# Multiplier_AD835.net
KiCad netlist of a schematic drawn in Altium Designer
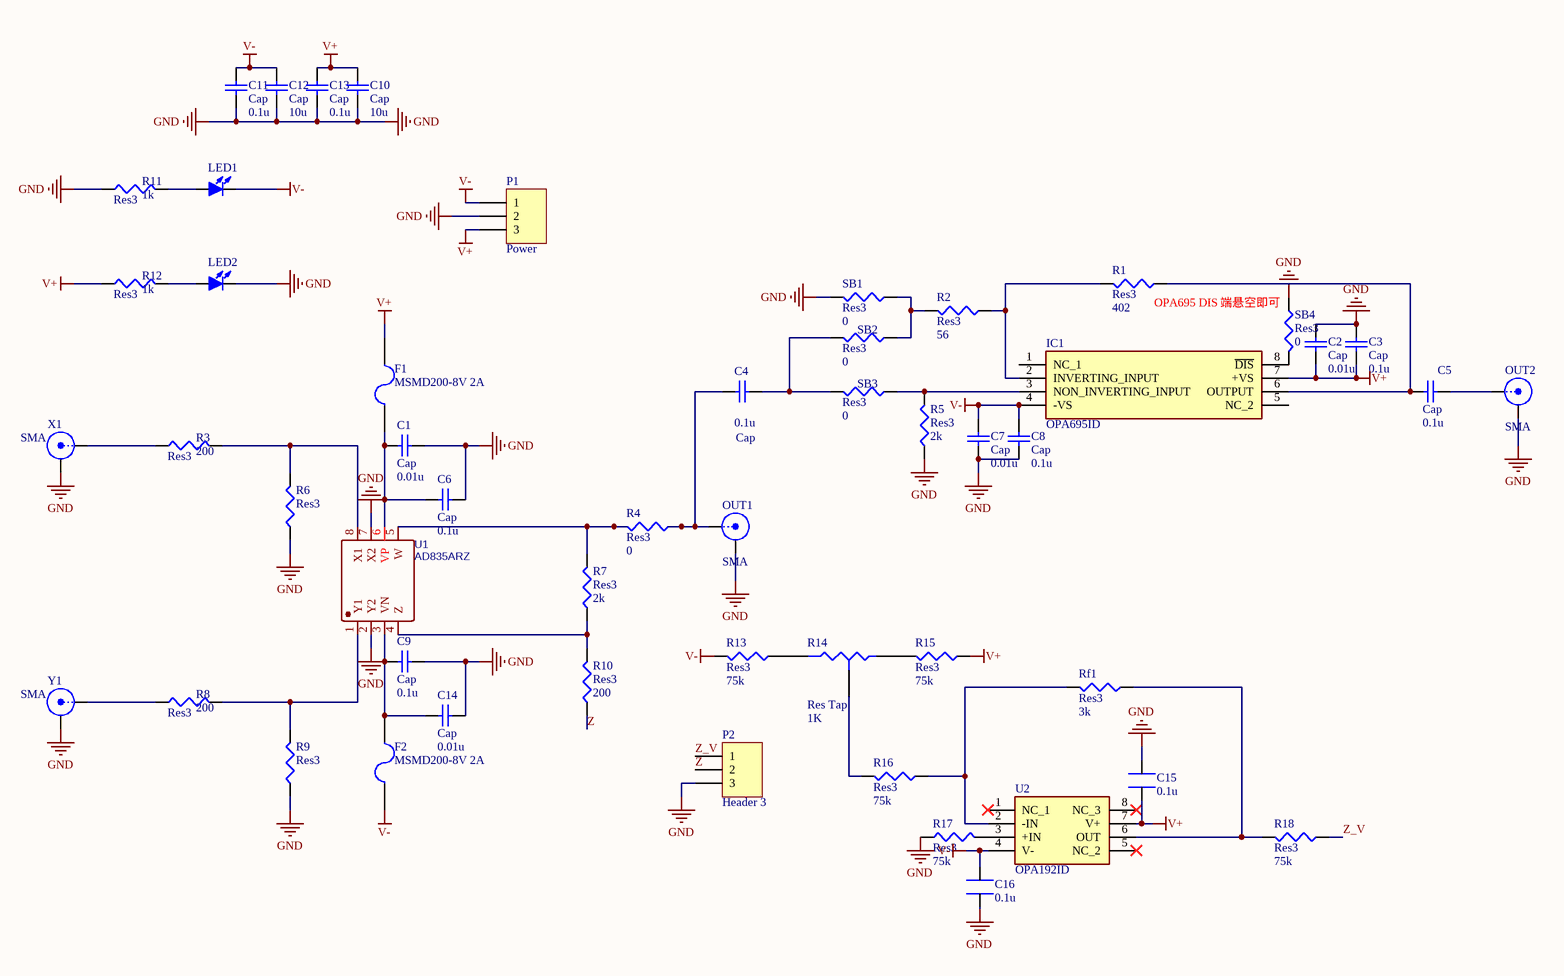
[diagram p0: Multiplier_AD835.SchDoc]

(export (version "E")
  (design (tool "Eeschema 10.0.6"))
  (components
    (comp (ref "C1")
      (value "Cap")
      (footprint "0805D")
      (description "Capacitor")
      (fields (field (name "ALTIUM_VALUE") "0.01u") (field (name "PUBLISHER") "Altium Limited"))
      (libsource (lib "Miscellaneous Devices") (part "Cap"))
    )
    (comp (ref "C2")
      (value "Cap")
      (footprint "0805D")
      (description "Capacitor")
      (fields (field (name "ALTIUM_VALUE") "0.01u") (field (name "PUBLISHER") "Altium Limited"))
      (libsource (lib "Miscellaneous Devices") (part "Cap"))
    )
    (comp (ref "C3")
      (value "Cap")
      (footprint "0805D")
      (description "Capacitor")
      (fields (field (name "ALTIUM_VALUE") "0.1u") (field (name "PUBLISHER") "Altium Limited"))
      (libsource (lib "Miscellaneous Devices") (part "Cap"))
    )
    (comp (ref "C4")
      (value "Cap")
      (footprint "0805D")
      (description "Capacitor")
      (fields (field (name "ALTIUM_VALUE") "0.1u") (field (name "PUBLISHER") "Altium Limited"))
      (libsource (lib "Miscellaneous Devices") (part "Cap"))
    )
    (comp (ref "C5")
      (value "Cap")
      (footprint "0805D")
      (description "Capacitor")
      (fields (field (name "ALTIUM_VALUE") "0.1u") (field (name "PUBLISHER") "Altium Limited"))
      (libsource (lib "Miscellaneous Devices") (part "Cap"))
    )
    (comp (ref "C6")
      (value "Cap")
      (footprint "0805D")
      (description "Capacitor")
      (fields (field (name "ALTIUM_VALUE") "0.1u") (field (name "PUBLISHER") "Altium Limited"))
      (libsource (lib "Miscellaneous Devices") (part "Cap"))
    )
    (comp (ref "C7")
      (value "Cap")
      (footprint "0805D")
      (description "Capacitor")
      (fields (field (name "ALTIUM_VALUE") "0.01u") (field (name "PUBLISHER") "Altium Limited"))
      (libsource (lib "Miscellaneous Devices") (part "Cap"))
    )
    (comp (ref "C8")
      (value "Cap")
      (footprint "0805D")
      (description "Capacitor")
      (fields (field (name "ALTIUM_VALUE") "0.1u") (field (name "PUBLISHER") "Altium Limited"))
      (libsource (lib "Miscellaneous Devices") (part "Cap"))
    )
    (comp (ref "C9")
      (value "Cap")
      (footprint "0805D")
      (description "Capacitor")
      (fields (field (name "ALTIUM_VALUE") "0.1u") (field (name "PUBLISHER") "Altium Limited"))
      (libsource (lib "Miscellaneous Devices") (part "Cap"))
    )
    (comp (ref "C10")
      (value "Cap")
      (footprint "0805D")
      (description "Capacitor")
      (fields (field (name "ALTIUM_VALUE") "10u") (field (name "PUBLISHER") "Altium Limited"))
      (libsource (lib "Miscellaneous Devices") (part "Cap"))
    )
    (comp (ref "C11")
      (value "Cap")
      (footprint "0805D")
      (description "Capacitor")
      (fields (field (name "ALTIUM_VALUE") "0.1u") (field (name "PUBLISHER") "Altium Limited"))
      (libsource (lib "Miscellaneous Devices") (part "Cap"))
    )
    (comp (ref "C12")
      (value "Cap")
      (footprint "0805D")
      (description "Capacitor")
      (fields (field (name "ALTIUM_VALUE") "10u") (field (name "PUBLISHER") "Altium Limited"))
      (libsource (lib "Miscellaneous Devices") (part "Cap"))
    )
    (comp (ref "C13")
      (value "Cap")
      (footprint "0805D")
      (description "Capacitor")
      (fields (field (name "ALTIUM_VALUE") "0.1u") (field (name "PUBLISHER") "Altium Limited"))
      (libsource (lib "Miscellaneous Devices") (part "Cap"))
    )
    (comp (ref "C14")
      (value "Cap")
      (footprint "0805D")
      (description "Capacitor")
      (fields (field (name "ALTIUM_VALUE") "0.01u") (field (name "PUBLISHER") "Altium Limited"))
      (libsource (lib "Miscellaneous Devices") (part "Cap"))
    )
    (comp (ref "C15") (value "0.1u") (footprint "0805D") (libsource (lib "Lib1") (part "CAP_T")))
    (comp (ref "C16") (value "0.1u") (footprint "0805D") (libsource (lib "Lib1") (part "CAP_T")))
    (comp (ref "F1")
      (value "MSMD200-8V 2A")
      (footprint "0805D")
      (description "贴片保险丝")
      (fields (field (name "版权归属") "源创客"))
      (libsource (lib "保险丝-晶振") (part "FU"))
    )
    (comp (ref "F2")
      (value "MSMD200-8V 2A")
      (footprint "0805D")
      (description "贴片保险丝")
      (fields (field (name "版权归属") "源创客"))
      (libsource (lib "保险丝-晶振") (part "FU"))
    )
    (comp (ref "IC1")
      (value "OPA695ID")
      (footprint "SamacSys:SOIC127P600X175-8N")
      (description "Integrated Circuit")
      (fields (field (name "MOUSER PART NUMBER") "595-OPA695ID"))
      (libsource (lib "SamacSys") (part "OPA695ID"))
    )
    (comp (ref "LED1")
      (value "~")
      (footprint "0805D")
      (description "贴片LED")
      (fields (field (name "版权归属") "源创客"))
      (libsource (lib "LED") (part "LED-SMD"))
    )
    (comp (ref "LED2")
      (value "~")
      (footprint "0805D")
      (description "贴片LED")
      (fields (field (name "版权归属") "源创客"))
      (libsource (lib "LED") (part "LED-SMD"))
    )
    (comp (ref "OUT1")
      (value "SMA")
      (footprint "SMA1")
      (description "BNC Elbow Connector")
      (fields (field (name "PUBLISHER") "Altium Limited"))
      (libsource (lib "Miscellaneous Connectors") (part "BNC"))
    )
    (comp (ref "OUT2")
      (value "SMA")
      (footprint "SMA1")
      (description "BNC Elbow Connector")
      (fields (field (name "PUBLISHER") "Altium Limited"))
      (libsource (lib "Miscellaneous Connectors") (part "BNC"))
    )
    (comp (ref "P1")
      (value "Power")
      (footprint "HDR1X3")
      (description "Header, 3-Pin")
      (fields (field (name "PUBLISHER") "Altium Limited"))
      (libsource (lib "Miscellaneous Connectors") (part "Header 3"))
    )
    (comp (ref "P2")
      (value "Header 3")
      (footprint "HDR1X3")
      (description "Header, 3-Pin")
      (fields (field (name "PUBLISHER") "Altium Limited"))
      (libsource (lib "Miscellaneous Connectors") (part "Header 3"))
    )
    (comp (ref "R1")
      (value "Res3")
      (footprint "0805D")
      (description "Resistor")
      (fields (field (name "ALTIUM_VALUE") "402") (field (name "PUBLISHER") "Altium Limited"))
      (libsource (lib "Miscellaneous Devices") (part "Res3"))
    )
    (comp (ref "R2")
      (value "Res3")
      (footprint "0805D")
      (description "Resistor")
      (fields (field (name "ALTIUM_VALUE") "56") (field (name "PUBLISHER") "Altium Limited"))
      (libsource (lib "Miscellaneous Devices") (part "Res3"))
    )
    (comp (ref "R3")
      (value "Res3")
      (footprint "0805D")
      (description "Resistor")
      (fields (field (name "ALTIUM_VALUE") "200") (field (name "PUBLISHER") "Altium Limited"))
      (libsource (lib "Miscellaneous Devices") (part "Res3"))
    )
    (comp (ref "R4")
      (value "Res3")
      (footprint "0805D")
      (description "Resistor")
      (fields (field (name "ALTIUM_VALUE") "0") (field (name "PUBLISHER") "Altium Limited"))
      (libsource (lib "Miscellaneous Devices") (part "Res3"))
    )
    (comp (ref "R5")
      (value "Res3")
      (footprint "0805D")
      (description "Resistor")
      (fields (field (name "ALTIUM_VALUE") "2k") (field (name "PUBLISHER") "Altium Limited"))
      (libsource (lib "Miscellaneous Devices") (part "Res3"))
    )
    (comp (ref "R6")
      (value "Res3")
      (footprint "0805D")
      (description "Resistor")
      (fields (field (name "PUBLISHER") "Altium Limited"))
      (libsource (lib "Miscellaneous Devices") (part "Res3"))
    )
    (comp (ref "R7")
      (value "Res3")
      (footprint "0805D")
      (description "Resistor")
      (fields (field (name "ALTIUM_VALUE") "2k") (field (name "PUBLISHER") "Altium Limited"))
      (libsource (lib "Miscellaneous Devices") (part "Res3"))
    )
    (comp (ref "R8")
      (value "Res3")
      (footprint "0805D")
      (description "Resistor")
      (fields (field (name "ALTIUM_VALUE") "200") (field (name "PUBLISHER") "Altium Limited"))
      (libsource (lib "Miscellaneous Devices") (part "Res3"))
    )
    (comp (ref "R9")
      (value "Res3")
      (footprint "0805D")
      (description "Resistor")
      (fields (field (name "PUBLISHER") "Altium Limited"))
      (libsource (lib "Miscellaneous Devices") (part "Res3"))
    )
    (comp (ref "R10")
      (value "Res3")
      (footprint "0805D")
      (description "Resistor")
      (fields (field (name "ALTIUM_VALUE") "200") (field (name "PUBLISHER") "Altium Limited"))
      (libsource (lib "Miscellaneous Devices") (part "Res3"))
    )
    (comp (ref "R11")
      (value "Res3")
      (footprint "0805D")
      (description "Resistor")
      (fields (field (name "ALTIUM_VALUE") "1k") (field (name "PUBLISHER") "Altium Limited"))
      (libsource (lib "Miscellaneous Devices") (part "Res3"))
    )
    (comp (ref "R12")
      (value "Res3")
      (footprint "0805D")
      (description "Resistor")
      (fields (field (name "ALTIUM_VALUE") "1k") (field (name "PUBLISHER") "Altium Limited"))
      (libsource (lib "Miscellaneous Devices") (part "Res3"))
    )
    (comp (ref "R13")
      (value "Res3")
      (footprint "0805D")
      (description "Resistor")
      (fields (field (name "ALTIUM_VALUE") "75k") (field (name "PUBLISHER") "Altium Limited"))
      (libsource (lib "Miscellaneous Devices") (part "Res3"))
    )
    (comp (ref "R14")
      (value "Res Tap")
      (description "Tapped Resistor")
      (fields (field (name "ALTIUM_VALUE") "1K") (field (name "PUBLISHER") "Altium Limited"))
      (libsource (lib "Miscellaneous Devices") (part "Res Tap"))
    )
    (comp (ref "R15")
      (value "Res3")
      (footprint "0805D")
      (description "Resistor")
      (fields (field (name "ALTIUM_VALUE") "75k") (field (name "PUBLISHER") "Altium Limited"))
      (libsource (lib "Miscellaneous Devices") (part "Res3"))
    )
    (comp (ref "R16")
      (value "Res3")
      (footprint "0805D")
      (description "Resistor")
      (fields (field (name "ALTIUM_VALUE") "75k") (field (name "PUBLISHER") "Altium Limited"))
      (libsource (lib "Miscellaneous Devices") (part "Res3"))
    )
    (comp (ref "R17")
      (value "Res3")
      (footprint "0805D")
      (description "Resistor")
      (fields (field (name "ALTIUM_VALUE") "75k") (field (name "PUBLISHER") "Altium Limited"))
      (libsource (lib "Miscellaneous Devices") (part "Res3"))
    )
    (comp (ref "R18")
      (value "Res3")
      (footprint "0805D")
      (description "Resistor")
      (fields (field (name "ALTIUM_VALUE") "75k") (field (name "PUBLISHER") "Altium Limited"))
      (libsource (lib "Miscellaneous Devices") (part "Res3"))
    )
    (comp (ref "Rf1")
      (value "Res3")
      (footprint "0805D")
      (description "Resistor")
      (fields (field (name "ALTIUM_VALUE") "3k") (field (name "PUBLISHER") "Altium Limited"))
      (libsource (lib "Miscellaneous Devices") (part "Res3"))
    )
    (comp (ref "SB1")
      (value "Res3")
      (footprint "0805D")
      (description "Resistor")
      (fields (field (name "ALTIUM_VALUE") "0") (field (name "PUBLISHER") "Altium Limited"))
      (libsource (lib "Miscellaneous Devices") (part "Res3"))
    )
    (comp (ref "SB2")
      (value "Res3")
      (footprint "0805D")
      (description "Resistor")
      (fields (field (name "ALTIUM_VALUE") "0") (field (name "PUBLISHER") "Altium Limited"))
      (libsource (lib "Miscellaneous Devices") (part "Res3"))
    )
    (comp (ref "SB3")
      (value "Res3")
      (footprint "0805D")
      (description "Resistor")
      (fields (field (name "ALTIUM_VALUE") "0") (field (name "PUBLISHER") "Altium Limited"))
      (libsource (lib "Miscellaneous Devices") (part "Res3"))
    )
    (comp (ref "SB4")
      (value "Res3")
      (footprint "0805D")
      (description "Resistor")
      (fields (field (name "ALTIUM_VALUE") "0") (field (name "PUBLISHER") "Altium Limited"))
      (libsource (lib "Miscellaneous Devices") (part "Res3"))
    )
    (comp (ref "U1")
      (value "AD835ARZ")
      (footprint "AD835arz")
      (fields (field (name "BOM_SUPPLIER PART") "C26332"))
      (libsource (lib "AD835ARZ") (part "AD835ARZ"))
    )
    (comp (ref "U2")
      (value "OPA192ID")
      (footprint "SamacSys:SOIC127P600X175-8N")
      (description "Undefined or Miscellaneous")
      (fields (field (name "MOUSER PART NUMBER") "595-OPA192ID"))
      (libsource (lib "*") (part "OPA192ID"))
    )
    (comp (ref "X1")
      (value "SMA")
      (footprint "SMA1")
      (description "BNC Elbow Connector")
      (fields (field (name "PUBLISHER") "Altium Limited"))
      (libsource (lib "Miscellaneous Connectors") (part "BNC"))
    )
    (comp (ref "Y1")
      (value "SMA")
      (footprint "SMA1")
      (description "BNC Elbow Connector")
      (fields (field (name "PUBLISHER") "Altium Limited"))
      (libsource (lib "Miscellaneous Connectors") (part "BNC"))
    )
  )
  (nets
    (net (code "1") (name "/Z") (class "Default")
      (node (ref "P2") (pin "2") (pinfunction "2_2") (pintype "passive"))
      (node (ref "R10") (pin "1") (pinfunction "1_1") (pintype "passive"))
    )
    (net (code "2") (name "/Z_V") (class "Default")
      (node (ref "P2") (pin "1") (pinfunction "1_1") (pintype "passive"))
      (node (ref "R18") (pin "1") (pinfunction "1_1") (pintype "passive"))
    )
    (net (code "3") (name "GND") (class "Default")
      (node (ref "C1") (pin "1") (pinfunction "1_1") (pintype "passive"))
      (node (ref "C10") (pin "1") (pinfunction "1_1") (pintype "passive"))
      (node (ref "C11") (pin "1") (pinfunction "1_1") (pintype "passive"))
      (node (ref "C12") (pin "1") (pinfunction "1_1") (pintype "passive"))
      (node (ref "C13") (pin "1") (pinfunction "1_1") (pintype "passive"))
      (node (ref "C14") (pin "2") (pinfunction "2_2") (pintype "passive"))
      (node (ref "C15") (pin "1") (pinfunction "SD_1") (pintype "passive"))
      (node (ref "C16") (pin "1") (pinfunction "SD_1") (pintype "passive"))
      (node (ref "C2") (pin "1") (pinfunction "1_1") (pintype "passive"))
      (node (ref "C3") (pin "2") (pinfunction "2_2") (pintype "passive"))
      (node (ref "C6") (pin "2") (pinfunction "2_2") (pintype "passive"))
      (node (ref "C7") (pin "2") (pinfunction "2_2") (pintype "passive"))
      (node (ref "C8") (pin "1") (pinfunction "1_1") (pintype "passive"))
      (node (ref "C9") (pin "1") (pinfunction "1_1") (pintype "passive"))
      (node (ref "LED2") (pin "2") (pinfunction "K_2") (pintype "passive"))
      (node (ref "OUT1") (pin "2") (pinfunction "Y_2") (pintype "passive"))
      (node (ref "OUT2") (pin "2") (pinfunction "Y_2") (pintype "passive"))
      (node (ref "P1") (pin "2") (pinfunction "2_2") (pintype "passive"))
      (node (ref "P2") (pin "3") (pinfunction "3_3") (pintype "passive"))
      (node (ref "R11") (pin "1") (pinfunction "1_1") (pintype "passive"))
      (node (ref "R17") (pin "2") (pinfunction "2_2") (pintype "passive"))
      (node (ref "R5") (pin "1") (pinfunction "1_1") (pintype "passive"))
      (node (ref "R6") (pin "1") (pinfunction "1_1") (pintype "passive"))
      (node (ref "R9") (pin "1") (pinfunction "1_1") (pintype "passive"))
      (node (ref "SB1") (pin "2") (pinfunction "2_2") (pintype "passive"))
      (node (ref "SB4") (pin "1") (pinfunction "1_1") (pintype "passive"))
      (node (ref "U1") (pin "2") (pinfunction "Y2_2") (pintype "passive"))
      (node (ref "U1") (pin "7") (pinfunction "X2_7") (pintype "passive"))
      (node (ref "X1") (pin "2") (pinfunction "Y_2") (pintype "passive"))
      (node (ref "Y1") (pin "2") (pinfunction "Y_2") (pintype "passive"))
    )
    (net (code "4") (name "Net-(C4-Pad2)") (class "Default")
      (node (ref "C4") (pin "2") (pinfunction "2_2") (pintype "passive"))
      (node (ref "SB2") (pin "2") (pinfunction "2_2") (pintype "passive"))
      (node (ref "SB3") (pin "2") (pinfunction "2_2") (pintype "passive"))
    )
    (net (code "5") (name "Net-(IC1-INVERTING_INPUT)") (class "Default")
      (node (ref "IC1") (pin "2") (pinfunction "INVERTING_INPUT_2") (pintype "passive"))
      (node (ref "R1") (pin "2") (pinfunction "2_2") (pintype "passive"))
      (node (ref "R2") (pin "1") (pinfunction "1_1") (pintype "passive"))
    )
    (net (code "6") (name "Net-(IC1-NON_INVERTING_INPUT)") (class "Default")
      (node (ref "IC1") (pin "3") (pinfunction "NON_INVERTING_INPUT_3") (pintype "passive"))
      (node (ref "R5") (pin "2") (pinfunction "2_2") (pintype "passive"))
      (node (ref "SB3") (pin "1") (pinfunction "1_1") (pintype "passive"))
    )
    (net (code "7") (name "Net-(IC1-OUTPUT)") (class "Default")
      (node (ref "C5") (pin "1") (pinfunction "1_1") (pintype "passive"))
      (node (ref "IC1") (pin "6") (pinfunction "OUTPUT_6") (pintype "passive"))
      (node (ref "R1") (pin "1") (pinfunction "1_1") (pintype "passive"))
    )
    (net (code "8") (name "Net-(IC1-~{DIS})") (class "Default")
      (node (ref "IC1") (pin "8") (pinfunction "~{DIS}_8") (pintype "passive"))
      (node (ref "SB4") (pin "2") (pinfunction "2_2") (pintype "passive"))
    )
    (net (code "9") (name "Net-(LED1-A)") (class "Default")
      (node (ref "LED1") (pin "1") (pinfunction "A_1") (pintype "passive"))
      (node (ref "R11") (pin "2") (pinfunction "2_2") (pintype "passive"))
    )
    (net (code "10") (name "Net-(LED2-A)") (class "Default")
      (node (ref "LED2") (pin "1") (pinfunction "A_1") (pintype "passive"))
      (node (ref "R12") (pin "2") (pinfunction "2_2") (pintype "passive"))
    )
    (net (code "11") (name "Net-(OUT1-X)") (class "Default")
      (node (ref "C4") (pin "1") (pinfunction "1_1") (pintype "passive"))
      (node (ref "OUT1") (pin "1") (pinfunction "X_1") (pintype "passive"))
      (node (ref "R4") (pin "1") (pinfunction "1_1") (pintype "passive"))
    )
    (net (code "12") (name "Net-(OUT2-X)") (class "Default")
      (node (ref "C5") (pin "2") (pinfunction "2_2") (pintype "passive"))
      (node (ref "OUT2") (pin "1") (pinfunction "X_1") (pintype "passive"))
    )
    (net (code "13") (name "Net-(R2-Pad2)") (class "Default")
      (node (ref "R2") (pin "2") (pinfunction "2_2") (pintype "passive"))
      (node (ref "SB1") (pin "1") (pinfunction "1_1") (pintype "passive"))
      (node (ref "SB2") (pin "1") (pinfunction "1_1") (pintype "passive"))
    )
    (net (code "14") (name "Net-(R14-A)") (class "Default")
      (node (ref "R14") (pin "1") (pinfunction "A_1") (pintype "passive"))
      (node (ref "R15") (pin "2") (pinfunction "2_2") (pintype "passive"))
    )
    (net (code "15") (name "Net-(R14-B)") (class "Default")
      (node (ref "R13") (pin "1") (pinfunction "1_1") (pintype "passive"))
      (node (ref "R14") (pin "2") (pinfunction "B_2") (pintype "passive"))
    )
    (net (code "16") (name "Net-(R14-TAP)") (class "Default")
      (node (ref "R14") (pin "3") (pinfunction "TAP_3") (pintype "passive"))
      (node (ref "R16") (pin "2") (pinfunction "2_2") (pintype "passive"))
    )
    (net (code "17") (name "Net-(U1-VN)") (class "Default")
      (node (ref "C14") (pin "1") (pinfunction "1_1") (pintype "passive"))
      (node (ref "C9") (pin "2") (pinfunction "2_2") (pintype "passive"))
      (node (ref "F2") (pin "2") (pinfunction "2_2") (pintype "passive"))
      (node (ref "U1") (pin "3") (pinfunction "VN_3") (pintype "passive"))
    )
    (net (code "18") (name "Net-(U1-VP)") (class "Default")
      (node (ref "C1") (pin "2") (pinfunction "2_2") (pintype "passive"))
      (node (ref "C6") (pin "1") (pinfunction "1_1") (pintype "passive"))
      (node (ref "F1") (pin "1") (pinfunction "1_1") (pintype "passive"))
      (node (ref "U1") (pin "6") (pinfunction "VP_6") (pintype "passive"))
    )
    (net (code "19") (name "Net-(U1-W)") (class "Default")
      (node (ref "R4") (pin "2") (pinfunction "2_2") (pintype "passive"))
      (node (ref "R7") (pin "2") (pinfunction "2_2") (pintype "passive"))
      (node (ref "U1") (pin "5") (pinfunction "W_5") (pintype "passive"))
    )
    (net (code "20") (name "Net-(U1-X1)") (class "Default")
      (node (ref "R3") (pin "2") (pinfunction "2_2") (pintype "passive"))
      (node (ref "R6") (pin "2") (pinfunction "2_2") (pintype "passive"))
      (node (ref "U1") (pin "8") (pinfunction "X1_8") (pintype "passive"))
    )
    (net (code "21") (name "Net-(U1-Y1)") (class "Default")
      (node (ref "R8") (pin "2") (pinfunction "2_2") (pintype "passive"))
      (node (ref "R9") (pin "2") (pinfunction "2_2") (pintype "passive"))
      (node (ref "U1") (pin "1") (pinfunction "Y1_1") (pintype "passive"))
    )
    (net (code "22") (name "Net-(U1-Z)") (class "Default")
      (node (ref "R10") (pin "2") (pinfunction "2_2") (pintype "passive"))
      (node (ref "R7") (pin "1") (pinfunction "1_1") (pintype "passive"))
      (node (ref "U1") (pin "4") (pinfunction "Z_4") (pintype "passive"))
    )
    (net (code "23") (name "Net-(U2-+IN)") (class "Default")
      (node (ref "R17") (pin "1") (pinfunction "1_1") (pintype "passive"))
      (node (ref "U2") (pin "3") (pinfunction "+IN_3") (pintype "passive"))
    )
    (net (code "24") (name "Net-(U2--IN)") (class "Default")
      (node (ref "R16") (pin "1") (pinfunction "1_1") (pintype "passive"))
      (node (ref "Rf1") (pin "2") (pinfunction "2_2") (pintype "passive"))
      (node (ref "U2") (pin "2") (pinfunction "-IN_2") (pintype "passive"))
    )
    (net (code "25") (name "Net-(U2-OUT)") (class "Default")
      (node (ref "R18") (pin "2") (pinfunction "2_2") (pintype "passive"))
      (node (ref "Rf1") (pin "1") (pinfunction "1_1") (pintype "passive"))
      (node (ref "U2") (pin "6") (pinfunction "OUT_6") (pintype "passive"))
    )
    (net (code "26") (name "Net-(X1-X)") (class "Default")
      (node (ref "R3") (pin "1") (pinfunction "1_1") (pintype "passive"))
      (node (ref "X1") (pin "1") (pinfunction "X_1") (pintype "passive"))
    )
    (net (code "27") (name "Net-(Y1-X)") (class "Default")
      (node (ref "R8") (pin "1") (pinfunction "1_1") (pintype "passive"))
      (node (ref "Y1") (pin "1") (pinfunction "X_1") (pintype "passive"))
    )
    (net (code "28") (name "V+") (class "Default")
      (node (ref "C10") (pin "2") (pinfunction "2_2") (pintype "passive"))
      (node (ref "C13") (pin "2") (pinfunction "2_2") (pintype "passive"))
      (node (ref "C15") (pin "2") (pinfunction "SD_2") (pintype "passive"))
      (node (ref "C2") (pin "2") (pinfunction "2_2") (pintype "passive"))
      (node (ref "C3") (pin "1") (pinfunction "1_1") (pintype "passive"))
      (node (ref "F1") (pin "2") (pinfunction "2_2") (pintype "passive"))
      (node (ref "IC1") (pin "7") (pinfunction "+VS_7") (pintype "passive"))
      (node (ref "P1") (pin "3") (pinfunction "3_3") (pintype "passive"))
      (node (ref "R12") (pin "1") (pinfunction "1_1") (pintype "passive"))
      (node (ref "R15") (pin "1") (pinfunction "1_1") (pintype "passive"))
      (node (ref "U2") (pin "7") (pinfunction "V+_7") (pintype "passive"))
    )
    (net (code "29") (name "V-") (class "Default")
      (node (ref "C11") (pin "2") (pinfunction "2_2") (pintype "passive"))
      (node (ref "C12") (pin "2") (pinfunction "2_2") (pintype "passive"))
      (node (ref "C16") (pin "2") (pinfunction "SD_2") (pintype "passive"))
      (node (ref "C7") (pin "1") (pinfunction "1_1") (pintype "passive"))
      (node (ref "C8") (pin "2") (pinfunction "2_2") (pintype "passive"))
      (node (ref "F2") (pin "1") (pinfunction "1_1") (pintype "passive"))
      (node (ref "IC1") (pin "4") (pinfunction "-VS_4") (pintype "passive"))
      (node (ref "LED1") (pin "2") (pinfunction "K_2") (pintype "passive"))
      (node (ref "P1") (pin "1") (pinfunction "1_1") (pintype "passive"))
      (node (ref "R13") (pin "2") (pinfunction "2_2") (pintype "passive"))
      (node (ref "U2") (pin "4") (pinfunction "V-_4") (pintype "passive"))
    )
    (net (code "30") (name "unconnected-(IC1-NC_1-Pad1)") (class "Default")
      (node (ref "IC1") (pin "1") (pinfunction "NC_1_1") (pintype "passive"))
    )
    (net (code "31") (name "unconnected-(IC1-NC_2-Pad5)") (class "Default")
      (node (ref "IC1") (pin "5") (pinfunction "NC_2_5") (pintype "passive"))
    )
    (net (code "32") (name "unconnected-(U2-NC_1-Pad1)") (class "Default")
      (node (ref "U2") (pin "1") (pinfunction "NC_1_1") (pintype "passive+no_connect"))
    )
    (net (code "33") (name "unconnected-(U2-NC_2-Pad5)") (class "Default")
      (node (ref "U2") (pin "5") (pinfunction "NC_2_5") (pintype "passive+no_connect"))
    )
    (net (code "34") (name "unconnected-(U2-NC_3-Pad8)") (class "Default")
      (node (ref "U2") (pin "8") (pinfunction "NC_3_8") (pintype "passive+no_connect"))
    )
  )
)
